# 3w-rgb-led-connector-mk-6_1.net
KiCad netlist of a schematic drawn in EAGLE
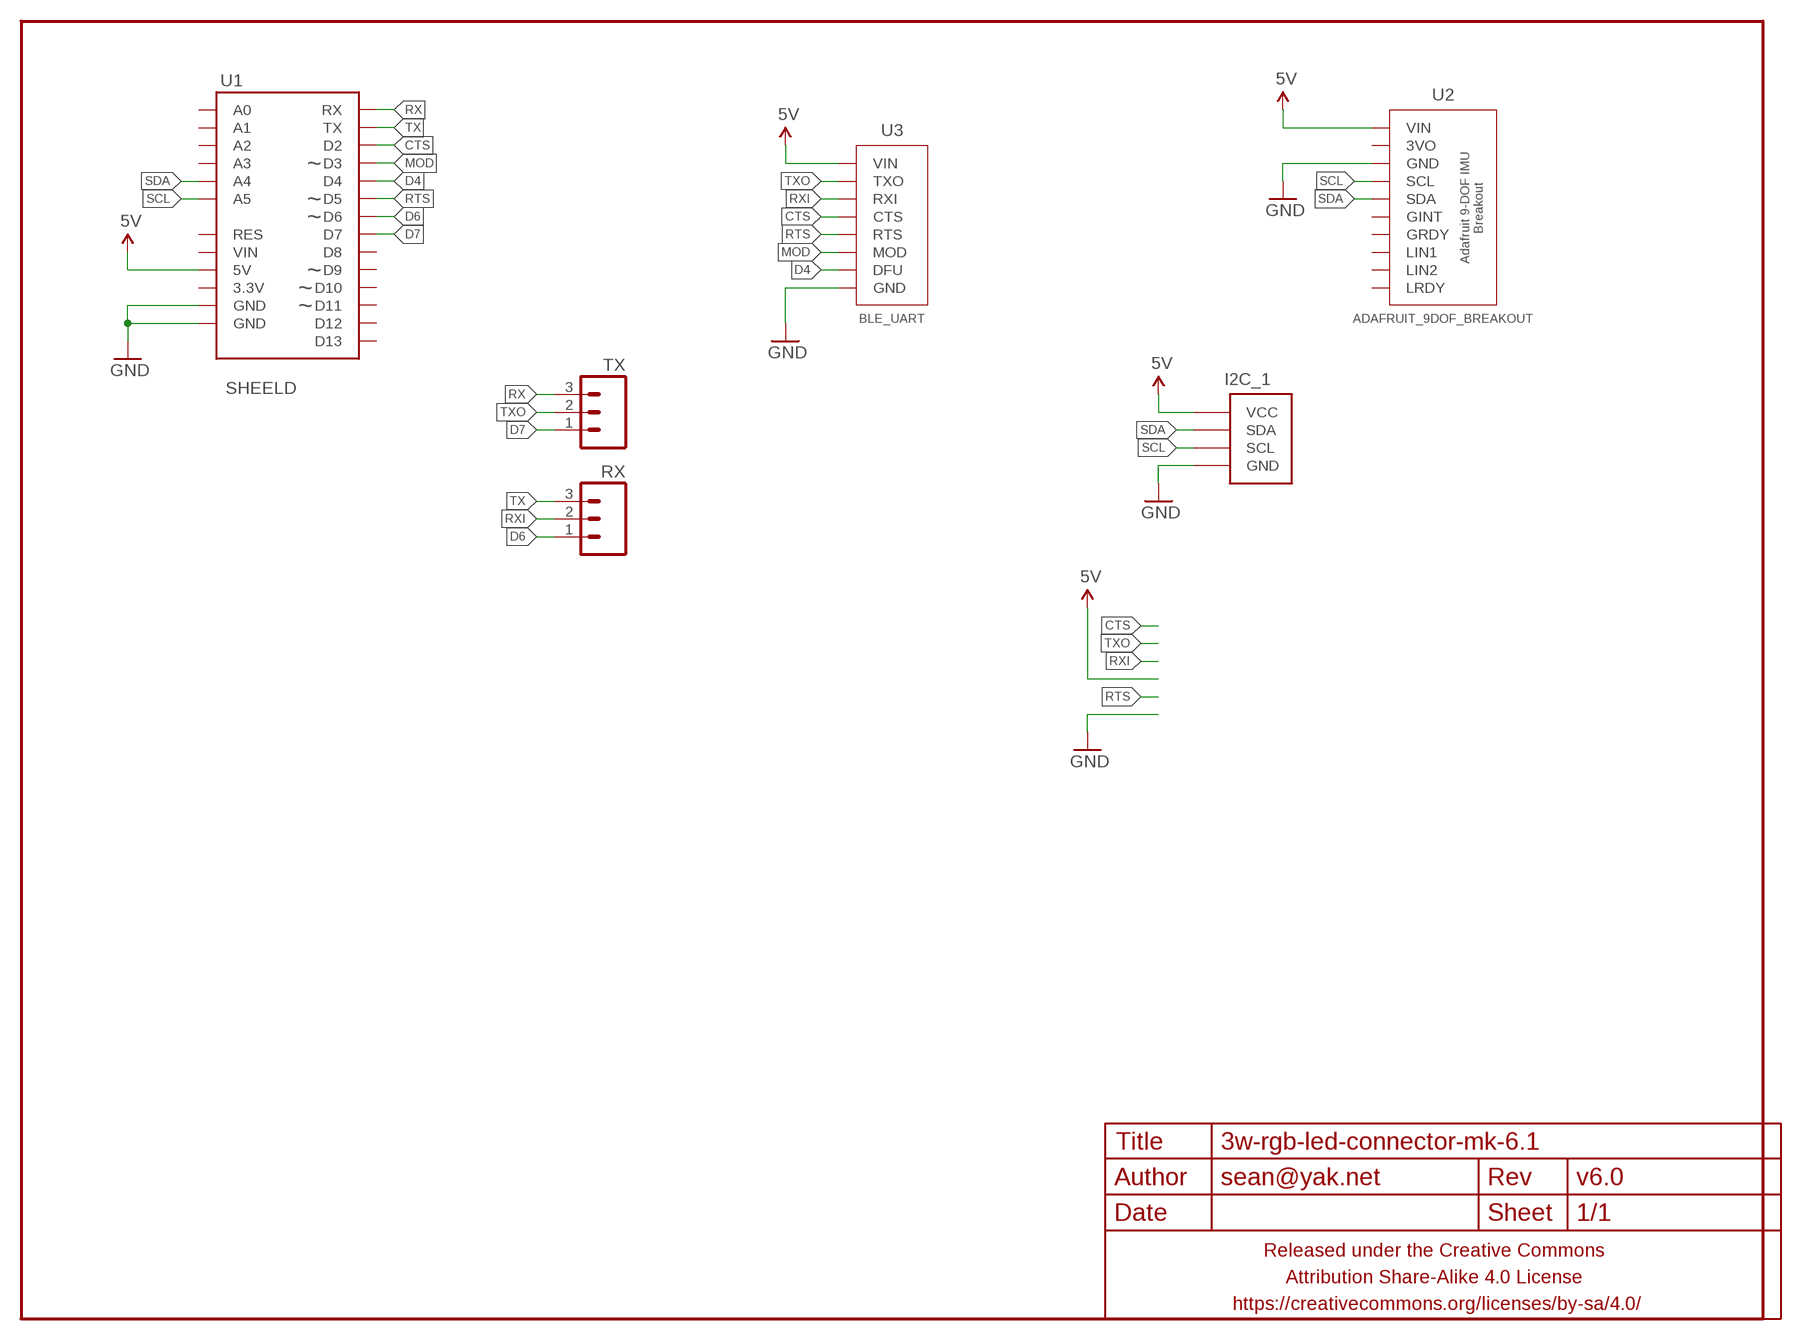
[diagram p0: schematic, sheet 1]

(export (version "E")
  (design (tool "Eeschema 10.0.6"))
  (components
    (comp (ref "FRAME1")
      (value "FRAME-LETTERNO_PACKAGE")
      (footprint "eagle-import:DUMMY")
      (fields (field (name "DESIGNER") "sean@yak.net") (field (name "VERSION") "v6.0"))
      (libsource (lib "eagle-import") (part "FRAME-LETTERNO_PACKAGE"))
    )
    (comp (ref "I2C_1")
      (value "M04-I2CPTH-0.1IN")
      (footprint "eagle-import:1X04-PTH-VERT-I2C")
      (libsource (lib "eagle-import") (part "M04-I2CPTH-0.1IN"))
    )
    (comp (ref "RX")
      (value "M03PTH-CENTERED")
      (footprint "eagle-import:1X03-CENTERED")
      (libsource (lib "eagle-import") (part "M03PTH-CENTERED"))
    )
    (comp (ref "TX")
      (value "M03PTH-CENTERED")
      (footprint "eagle-import:1X03-CENTERED")
      (libsource (lib "eagle-import") (part "M03PTH-CENTERED"))
    )
    (comp (ref "U1")
      (value "SHEELD")
      (footprint "eagle-import:ARDUINO_SHIELD_NOOUTLINE_INSIDE_SMALLER")
      (libsource (lib "eagle-import") (part "ARDUINO_SHIELD_SMALLER"))
    )
    (comp (ref "U2")
      (value "ADAFRUIT_9DOF_BREAKOUT")
      (footprint "eagle-import:ADAFRUIT_9DOF_BREAKOUT")
      (libsource (lib "eagle-import") (part "ADAFRUIT_9DOF_BREAKOUT"))
    )
    (comp (ref "U3")
      (value "BLE_UART")
      (footprint "eagle-import:ADAFRUIT_BLE_UART_NOTHOLEY")
      (libsource (lib "eagle-import") (part "ADAFRUIT_BLE_UARTLESSBARE"))
    )
  )
  (nets
    (net (code "1") (name "5V") (class "Default")
      (node (ref "I2C_1") (pin "VCC") (pinfunction "VCC_VCC") (pintype "bidirectional"))
      (node (ref "U1") (pin "5V") (pinfunction "5V_5V") (pintype "bidirectional"))
      (node (ref "U2") (pin "VIN") (pinfunction "VIN_VIN") (pintype "bidirectional"))
      (node (ref "U3") (pin "VIN") (pinfunction "VIN_VIN") (pintype "bidirectional"))
    )
    (net (code "2") (name "CTS") (class "Default")
      (node (ref "U1") (pin "D2") (pinfunction "D2_D2") (pintype "bidirectional"))
      (node (ref "U3") (pin "CTS") (pinfunction "CTS_CTS") (pintype "bidirectional"))
    )
    (net (code "3") (name "D4") (class "Default")
      (node (ref "U1") (pin "D4") (pinfunction "D4_D4") (pintype "bidirectional"))
      (node (ref "U3") (pin "DFU") (pinfunction "DFU_DFU") (pintype "bidirectional"))
    )
    (net (code "4") (name "D6") (class "Default")
      (node (ref "RX") (pin "1") (pinfunction "1_1") (pintype "passive"))
      (node (ref "U1") (pin "D6") (pinfunction "D6_D6") (pintype "bidirectional"))
    )
    (net (code "5") (name "D7") (class "Default")
      (node (ref "TX") (pin "1") (pinfunction "1_1") (pintype "passive"))
      (node (ref "U1") (pin "D7") (pinfunction "D7_D7") (pintype "bidirectional"))
    )
    (net (code "6") (name "GND") (class "Default")
      (node (ref "I2C_1") (pin "GND") (pinfunction "GND_GND") (pintype "bidirectional"))
      (node (ref "U1") (pin "GND@0") (pinfunction "GND_GND@0") (pintype "bidirectional"))
      (node (ref "U1") (pin "GND@1") (pinfunction "GND_GND@1") (pintype "bidirectional"))
      (node (ref "U2") (pin "GND") (pinfunction "GND_GND") (pintype "bidirectional"))
      (node (ref "U3") (pin "GND") (pinfunction "GND_GND") (pintype "bidirectional"))
    )
    (net (code "7") (name "MOD") (class "Default")
      (node (ref "U1") (pin "D3") (pinfunction "D3_D3") (pintype "bidirectional"))
      (node (ref "U3") (pin "MOD") (pinfunction "MOD_MOD") (pintype "bidirectional"))
    )
    (net (code "8") (name "RTS") (class "Default")
      (node (ref "U1") (pin "D5") (pinfunction "D5_D5") (pintype "bidirectional"))
      (node (ref "U3") (pin "RTS") (pinfunction "RTS_RTS") (pintype "bidirectional"))
    )
    (net (code "9") (name "RX") (class "Default")
      (node (ref "TX") (pin "3") (pinfunction "3_3") (pintype "passive"))
      (node (ref "U1") (pin "RX") (pinfunction "RX_RX") (pintype "bidirectional"))
    )
    (net (code "10") (name "RXI") (class "Default")
      (node (ref "RX") (pin "2") (pinfunction "2_2") (pintype "passive"))
      (node (ref "U3") (pin "RXI") (pinfunction "RXI_RXI") (pintype "bidirectional"))
    )
    (net (code "11") (name "SCL") (class "Default")
      (node (ref "I2C_1") (pin "SCL") (pinfunction "SCL_SCL") (pintype "bidirectional"))
      (node (ref "U1") (pin "A5") (pinfunction "A5_A5") (pintype "bidirectional"))
      (node (ref "U2") (pin "SCL") (pinfunction "SCL_SCL") (pintype "bidirectional"))
    )
    (net (code "12") (name "SDA") (class "Default")
      (node (ref "I2C_1") (pin "SDA") (pinfunction "SDA_SDA") (pintype "bidirectional"))
      (node (ref "U1") (pin "A4") (pinfunction "A4_A4") (pintype "bidirectional"))
      (node (ref "U2") (pin "SDA") (pinfunction "SDA_SDA") (pintype "bidirectional"))
    )
    (net (code "13") (name "TX") (class "Default")
      (node (ref "RX") (pin "3") (pinfunction "3_3") (pintype "passive"))
      (node (ref "U1") (pin "TX") (pinfunction "TX_TX") (pintype "bidirectional"))
    )
    (net (code "14") (name "TXO") (class "Default")
      (node (ref "TX") (pin "2") (pinfunction "2_2") (pintype "passive"))
      (node (ref "U3") (pin "TXO") (pinfunction "TXO_TXO") (pintype "bidirectional"))
    )
    (net (code "15") (name "unconnected-(U1-Pad3.3V)") (class "Default")
      (node (ref "U1") (pin "3.3V") (pinfunction "3.3V_3.3V") (pintype "bidirectional"))
    )
    (net (code "16") (name "unconnected-(U1-PadA0)") (class "Default")
      (node (ref "U1") (pin "A0") (pinfunction "A0_A0") (pintype "bidirectional"))
    )
    (net (code "17") (name "unconnected-(U1-PadA1)") (class "Default")
      (node (ref "U1") (pin "A1") (pinfunction "A1_A1") (pintype "bidirectional"))
    )
    (net (code "18") (name "unconnected-(U1-PadA2)") (class "Default")
      (node (ref "U1") (pin "A2") (pinfunction "A2_A2") (pintype "bidirectional"))
    )
    (net (code "19") (name "unconnected-(U1-PadA3)") (class "Default")
      (node (ref "U1") (pin "A3") (pinfunction "A3_A3") (pintype "bidirectional"))
    )
    (net (code "20") (name "unconnected-(U1-PadD8)") (class "Default")
      (node (ref "U1") (pin "D8") (pinfunction "D8_D8") (pintype "bidirectional"))
    )
    (net (code "21") (name "unconnected-(U1-PadD9)") (class "Default")
      (node (ref "U1") (pin "D9") (pinfunction "D9_D9") (pintype "bidirectional"))
    )
    (net (code "22") (name "unconnected-(U1-PadD10)") (class "Default")
      (node (ref "U1") (pin "D10") (pinfunction "D10_D10") (pintype "bidirectional"))
    )
    (net (code "23") (name "unconnected-(U1-PadD11)") (class "Default")
      (node (ref "U1") (pin "D11") (pinfunction "D11_D11") (pintype "bidirectional"))
    )
    (net (code "24") (name "unconnected-(U1-PadD12)") (class "Default")
      (node (ref "U1") (pin "D12") (pinfunction "D12_D12") (pintype "bidirectional"))
    )
    (net (code "25") (name "unconnected-(U1-PadD13)") (class "Default")
      (node (ref "U1") (pin "D13") (pinfunction "D13_D13") (pintype "bidirectional"))
    )
    (net (code "26") (name "unconnected-(U1-PadRES)") (class "Default")
      (node (ref "U1") (pin "RES") (pinfunction "RES_RES") (pintype "bidirectional"))
    )
    (net (code "27") (name "unconnected-(U1-PadVIN)") (class "Default")
      (node (ref "U1") (pin "VIN") (pinfunction "VIN_VIN") (pintype "bidirectional"))
    )
    (net (code "28") (name "unconnected-(U2-Pad3VO)") (class "Default")
      (node (ref "U2") (pin "3VO") (pinfunction "3VO_3VO") (pintype "bidirectional"))
    )
    (net (code "29") (name "unconnected-(U2-PadGINT)") (class "Default")
      (node (ref "U2") (pin "GINT") (pinfunction "GINT_GINT") (pintype "bidirectional"))
    )
    (net (code "30") (name "unconnected-(U2-PadGRDY)") (class "Default")
      (node (ref "U2") (pin "GRDY") (pinfunction "GRDY_GRDY") (pintype "bidirectional"))
    )
    (net (code "31") (name "unconnected-(U2-PadLIN1)") (class "Default")
      (node (ref "U2") (pin "LIN1") (pinfunction "LIN1_LIN1") (pintype "bidirectional"))
    )
    (net (code "32") (name "unconnected-(U2-PadLIN2)") (class "Default")
      (node (ref "U2") (pin "LIN2") (pinfunction "LIN2_LIN2") (pintype "bidirectional"))
    )
    (net (code "33") (name "unconnected-(U2-PadLRDY)") (class "Default")
      (node (ref "U2") (pin "LRDY") (pinfunction "LRDY_LRDY") (pintype "bidirectional"))
    )
  )
)
